# fibre_sensor_board.net
KiCad netlist of a schematic drawn in EAGLE
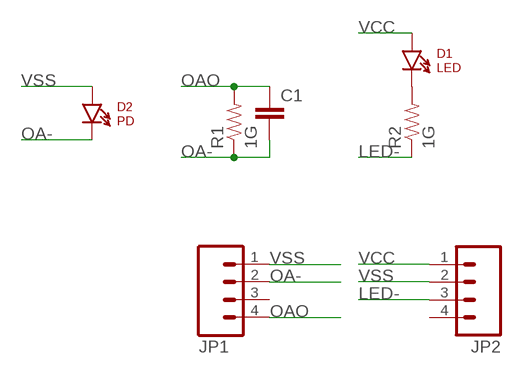
[diagram p0: schematic, sheet 1]

(export (version "E")
  (design (tool "Eeschema 10.0.6"))
  (components
    (comp (ref "C1")
      (value "CAPPTH")
      (footprint "eagle-import:CAP-PTH-SMALL")
      (libsource (lib "eagle-import") (part "CAPPTH"))
    )
    (comp (ref "D1")
      (value "LED")
      (footprint "eagle-import:LTE-302")
      (libsource (lib "eagle-import") (part "LTE-302"))
    )
    (comp (ref "D2")
      (value "PD")
      (footprint "eagle-import:LTE-302")
      (libsource (lib "eagle-import") (part "LTE-302"))
    )
    (comp (ref "JP1")
      (value "M04PTH")
      (footprint "eagle-import:1X04")
      (libsource (lib "eagle-import") (part "M04PTH"))
    )
    (comp (ref "JP2")
      (value "M04PTH")
      (footprint "eagle-import:1X04")
      (libsource (lib "eagle-import") (part "M04PTH"))
    )
    (comp (ref "R1")
      (value "1G")
      (footprint "eagle-import:AXIAL-0.3")
      (libsource (lib "eagle-import") (part "RESISTORAXIAL-0.3"))
    )
    (comp (ref "R2")
      (value "1G")
      (footprint "eagle-import:AXIAL-0.3")
      (libsource (lib "eagle-import") (part "RESISTORAXIAL-0.3"))
    )
  )
  (nets
    (net (code "1") (name "/LED-") (class "Default")
      (node (ref "JP2") (pin "3") (pinfunction "3_3") (pintype "passive"))
      (node (ref "R2") (pin "P$1") (pinfunction "1_P$1") (pintype "passive"))
    )
    (net (code "2") (name "/OA-") (class "Default")
      (node (ref "C1") (pin "2") (pinfunction "2_2") (pintype "passive"))
      (node (ref "D2") (pin "C") (pinfunction "C_C") (pintype "bidirectional"))
      (node (ref "JP1") (pin "2") (pinfunction "2_2") (pintype "passive"))
      (node (ref "R1") (pin "P$1") (pinfunction "1_P$1") (pintype "passive"))
    )
    (net (code "3") (name "/OAO") (class "Default")
      (node (ref "C1") (pin "1") (pinfunction "1_1") (pintype "passive"))
      (node (ref "JP1") (pin "4") (pinfunction "4_4") (pintype "passive"))
      (node (ref "R1") (pin "P$2") (pinfunction "2_P$2") (pintype "passive"))
    )
    (net (code "4") (name "/VCC") (class "Default")
      (node (ref "D1") (pin "A") (pinfunction "A_A") (pintype "bidirectional"))
      (node (ref "JP2") (pin "1") (pinfunction "1_1") (pintype "passive"))
    )
    (net (code "5") (name "/VSS") (class "Default")
      (node (ref "D2") (pin "A") (pinfunction "A_A") (pintype "bidirectional"))
      (node (ref "JP1") (pin "1") (pinfunction "1_1") (pintype "passive"))
      (node (ref "JP2") (pin "2") (pinfunction "2_2") (pintype "passive"))
    )
    (net (code "6") (name "Net-(R2-2)") (class "Default")
      (node (ref "D1") (pin "C") (pinfunction "C_C") (pintype "bidirectional"))
      (node (ref "R2") (pin "P$2") (pinfunction "2_P$2") (pintype "passive"))
    )
    (net (code "7") (name "unconnected-(JP1-Pad3)") (class "Default")
      (node (ref "JP1") (pin "3") (pinfunction "3_3") (pintype "passive"))
    )
    (net (code "8") (name "unconnected-(JP2-Pad4)") (class "Default")
      (node (ref "JP2") (pin "4") (pinfunction "4_4") (pintype "passive"))
    )
  )
)
